# battery_board.net
KiCad netlist of a schematic drawn in EAGLE
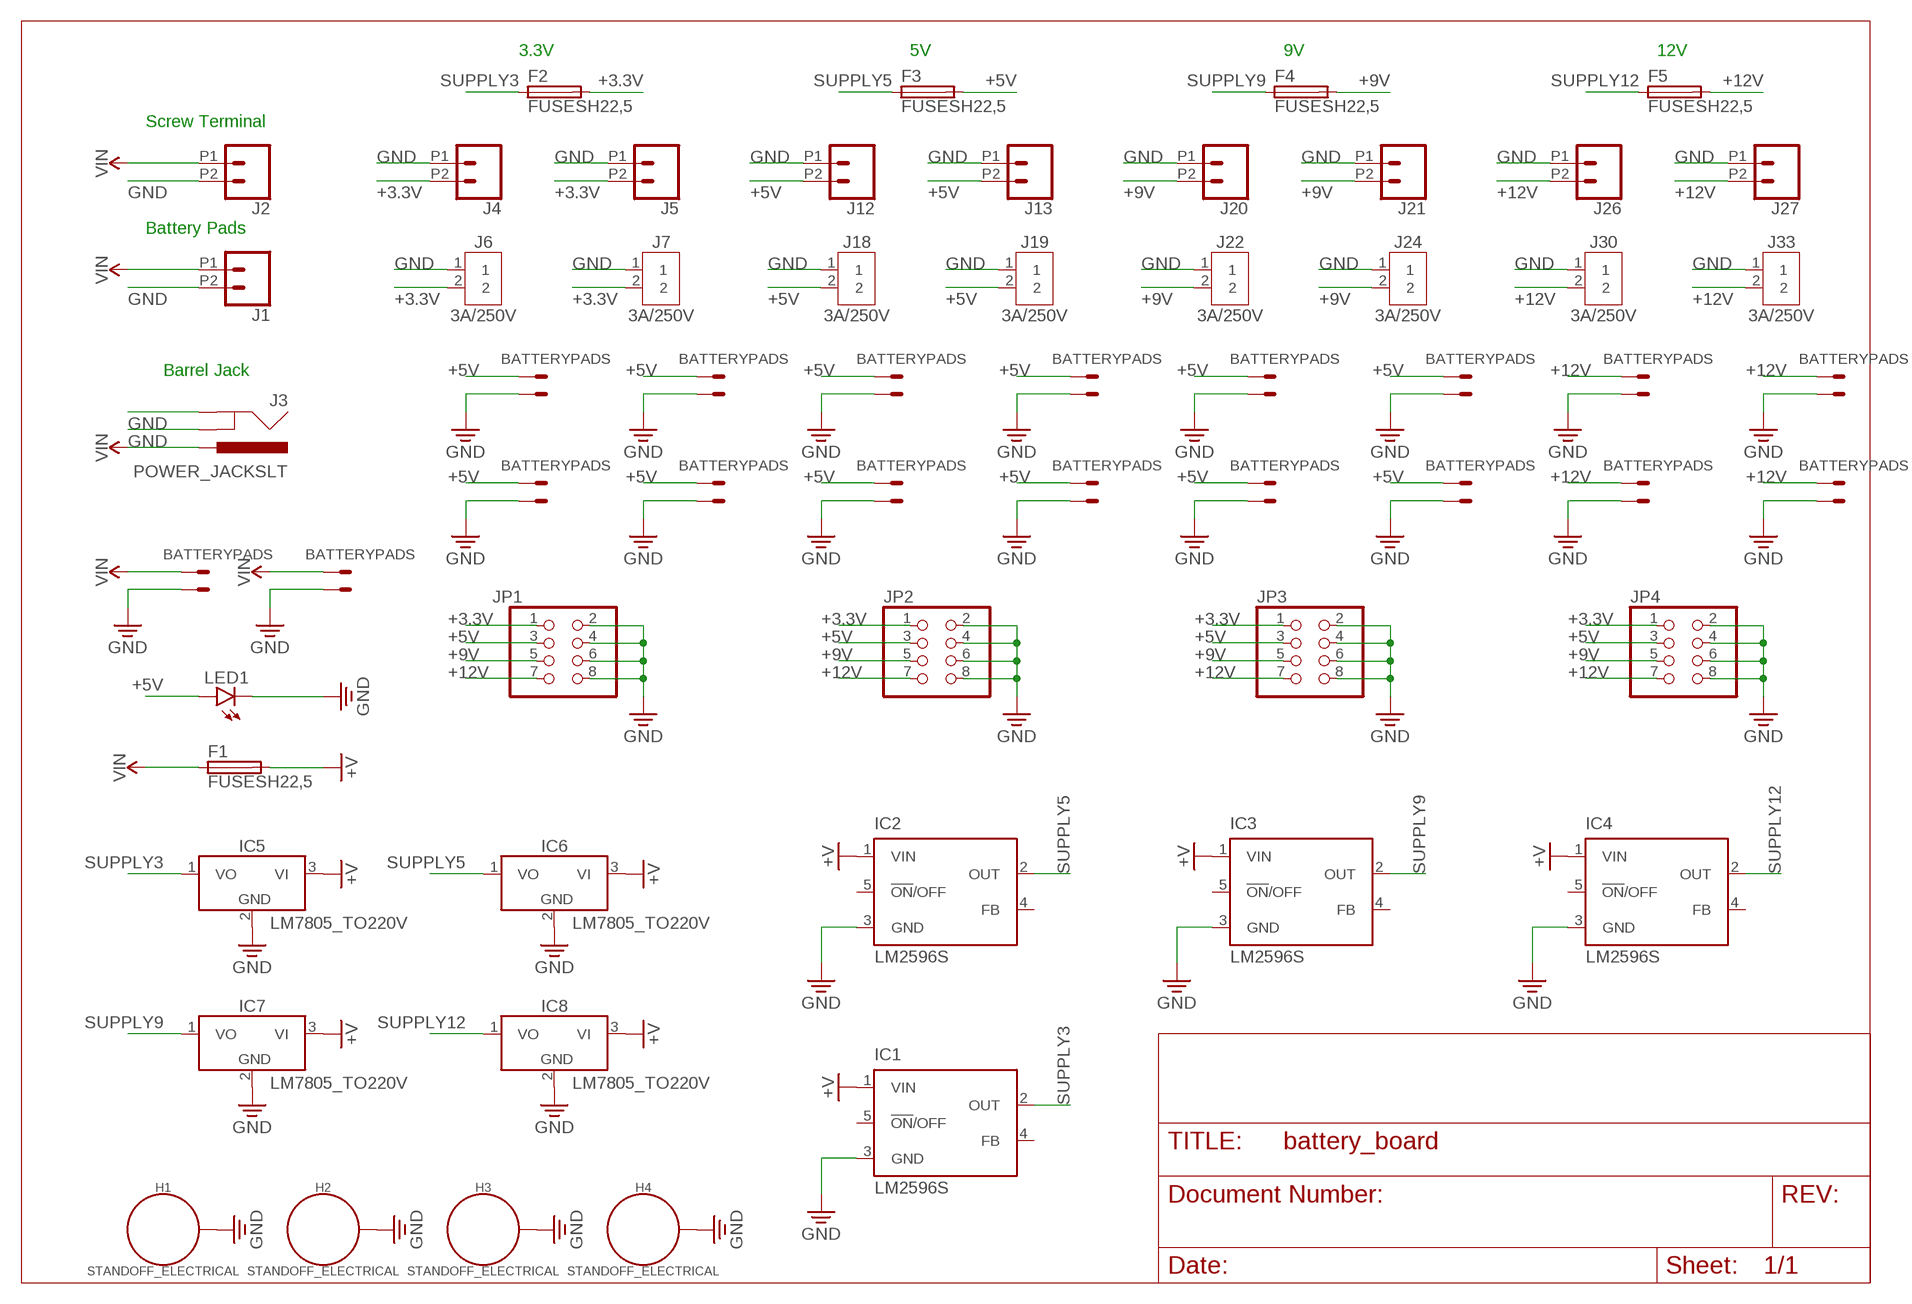
[diagram p0: schematic, sheet 1]

(export (version "E")
  (design (tool "Eeschema 10.0.6"))
  (components
    (comp (ref "BATTERY1")
      (value "BATTERYPADS")
      (footprint "eagle-import:DIODFN1228X508X30-2N")
      (libsource (lib "eagle-import") (part "BATTERYPADS"))
    )
    (comp (ref "BATTERY2")
      (value "BATTERYPADS")
      (footprint "eagle-import:DIODFN1228X508X30-2N")
      (libsource (lib "eagle-import") (part "BATTERYPADS"))
    )
    (comp (ref "F1")
      (value "FUSESH22,5")
      (footprint "eagle-import:SH22,5")
      (libsource (lib "eagle-import") (part "FUSESH22,5"))
    )
    (comp (ref "F2")
      (value "FUSESH22,5")
      (footprint "eagle-import:SH22,5")
      (libsource (lib "eagle-import") (part "FUSESH22,5"))
    )
    (comp (ref "F3")
      (value "FUSESH22,5")
      (footprint "eagle-import:SH22,5")
      (libsource (lib "eagle-import") (part "FUSESH22,5"))
    )
    (comp (ref "F4")
      (value "FUSESH22,5")
      (footprint "eagle-import:SH22,5")
      (libsource (lib "eagle-import") (part "FUSESH22,5"))
    )
    (comp (ref "F5")
      (value "FUSESH22,5")
      (footprint "eagle-import:SH22,5")
      (libsource (lib "eagle-import") (part "FUSESH22,5"))
    )
    (comp (ref "H1")
      (value "STANDOFF_ELECTRICAL")
      (footprint "eagle-import:STANDOFF-ELECTRICAL")
      (libsource (lib "eagle-import") (part "STANDOFF_ELECTRICAL"))
    )
    (comp (ref "H2")
      (value "STANDOFF_ELECTRICAL")
      (footprint "eagle-import:STANDOFF-ELECTRICAL")
      (libsource (lib "eagle-import") (part "STANDOFF_ELECTRICAL"))
    )
    (comp (ref "H3")
      (value "STANDOFF_ELECTRICAL")
      (footprint "eagle-import:STANDOFF-ELECTRICAL")
      (libsource (lib "eagle-import") (part "STANDOFF_ELECTRICAL"))
    )
    (comp (ref "H4")
      (value "STANDOFF_ELECTRICAL")
      (footprint "eagle-import:STANDOFF-ELECTRICAL")
      (libsource (lib "eagle-import") (part "STANDOFF_ELECTRICAL"))
    )
    (comp (ref "IC1")
      (value "LM2596S")
      (footprint "eagle-import:TO263-5")
      (fields (field (name "MF") "NATIONAL SEMICONDUCTOR") (field (name "MPN") "LM2596S-ADJ/NOPB"))
      (libsource (lib "eagle-import") (part "LM2596S"))
    )
    (comp (ref "IC2")
      (value "LM2596S")
      (footprint "eagle-import:TO263-5")
      (fields (field (name "MF") "NATIONAL SEMICONDUCTOR") (field (name "MPN") "LM2596S-ADJ/NOPB"))
      (libsource (lib "eagle-import") (part "LM2596S"))
    )
    (comp (ref "IC3")
      (value "LM2596S")
      (footprint "eagle-import:TO263-5")
      (fields (field (name "MF") "NATIONAL SEMICONDUCTOR") (field (name "MPN") "LM2596S-ADJ/NOPB"))
      (libsource (lib "eagle-import") (part "LM2596S"))
    )
    (comp (ref "IC4")
      (value "LM2596S")
      (footprint "eagle-import:TO263-5")
      (fields (field (name "MF") "NATIONAL SEMICONDUCTOR") (field (name "MPN") "LM2596S-ADJ/NOPB"))
      (libsource (lib "eagle-import") (part "LM2596S"))
    )
    (comp (ref "IC5")
      (value "LM7805_TO220V")
      (footprint "eagle-import:TO220V")
      (fields (field (name "MANUFACTURER") "Generic"))
      (libsource (lib "eagle-import") (part "LM7805_TO220V"))
    )
    (comp (ref "IC6")
      (value "LM7805_TO220V")
      (footprint "eagle-import:TO220V")
      (fields (field (name "MANUFACTURER") "Generic"))
      (libsource (lib "eagle-import") (part "LM7805_TO220V"))
    )
    (comp (ref "IC7")
      (value "LM7805_TO220V")
      (footprint "eagle-import:TO220V")
      (fields (field (name "MANUFACTURER") "Generic"))
      (libsource (lib "eagle-import") (part "LM7805_TO220V"))
    )
    (comp (ref "IC8")
      (value "LM7805_TO220V")
      (footprint "eagle-import:TO220V")
      (fields (field (name "MANUFACTURER") "Generic"))
      (libsource (lib "eagle-import") (part "LM7805_TO220V"))
    )
    (comp (ref "J1")
      (value "CONN_022.54MM_SCREWTERM")
      (footprint "eagle-import:1X02_2.54_SCREWTERM")
      (libsource (lib "eagle-import") (part "CONN_022.54MM_SCREWTERM"))
    )
    (comp (ref "J2")
      (value "CONN_022.54MM_SCREWTERM")
      (footprint "eagle-import:1X02_2.54_SCREWTERM")
      (libsource (lib "eagle-import") (part "CONN_022.54MM_SCREWTERM"))
    )
    (comp (ref "J3")
      (value "POWER_JACKSLT")
      (footprint "eagle-import:POWER_JACK_SLOT")
      (libsource (lib "eagle-import") (part "POWER_JACKSLT"))
    )
    (comp (ref "J4")
      (value "CONN_022.54MM_SCREWTERM")
      (footprint "eagle-import:1X02_2.54_SCREWTERM")
      (libsource (lib "eagle-import") (part "CONN_022.54MM_SCREWTERM"))
    )
    (comp (ref "J5")
      (value "CONN_022.54MM_SCREWTERM")
      (footprint "eagle-import:1X02_2.54_SCREWTERM")
      (libsource (lib "eagle-import") (part "CONN_022.54MM_SCREWTERM"))
    )
    (comp (ref "J6")
      (value "3A/250V")
      (footprint "eagle-import:B2B-XH-A")
      (fields (field (name "MANUFACTURER") "JST (XH CONNECTOR)") (field (name "MPN") "B2B-XH-A"))
      (libsource (lib "eagle-import") (part "B2B-XH-A"))
    )
    (comp (ref "J7")
      (value "3A/250V")
      (footprint "eagle-import:B2B-XH-A")
      (fields (field (name "MANUFACTURER") "JST (XH CONNECTOR)") (field (name "MPN") "B2B-XH-A"))
      (libsource (lib "eagle-import") (part "B2B-XH-A"))
    )
    (comp (ref "J12")
      (value "CONN_022.54MM_SCREWTERM")
      (footprint "eagle-import:1X02_2.54_SCREWTERM")
      (libsource (lib "eagle-import") (part "CONN_022.54MM_SCREWTERM"))
    )
    (comp (ref "J13")
      (value "CONN_022.54MM_SCREWTERM")
      (footprint "eagle-import:1X02_2.54_SCREWTERM")
      (libsource (lib "eagle-import") (part "CONN_022.54MM_SCREWTERM"))
    )
    (comp (ref "J18")
      (value "3A/250V")
      (footprint "eagle-import:B2B-XH-A")
      (fields (field (name "MANUFACTURER") "JST (XH CONNECTOR)") (field (name "MPN") "B2B-XH-A"))
      (libsource (lib "eagle-import") (part "B2B-XH-A"))
    )
    (comp (ref "J19")
      (value "3A/250V")
      (footprint "eagle-import:B2B-XH-A")
      (fields (field (name "MANUFACTURER") "JST (XH CONNECTOR)") (field (name "MPN") "B2B-XH-A"))
      (libsource (lib "eagle-import") (part "B2B-XH-A"))
    )
    (comp (ref "J20")
      (value "CONN_022.54MM_SCREWTERM")
      (footprint "eagle-import:1X02_2.54_SCREWTERM")
      (libsource (lib "eagle-import") (part "CONN_022.54MM_SCREWTERM"))
    )
    (comp (ref "J21")
      (value "CONN_022.54MM_SCREWTERM")
      (footprint "eagle-import:1X02_2.54_SCREWTERM")
      (libsource (lib "eagle-import") (part "CONN_022.54MM_SCREWTERM"))
    )
    (comp (ref "J22")
      (value "3A/250V")
      (footprint "eagle-import:B2B-XH-A")
      (fields (field (name "MANUFACTURER") "JST (XH CONNECTOR)") (field (name "MPN") "B2B-XH-A"))
      (libsource (lib "eagle-import") (part "B2B-XH-A"))
    )
    (comp (ref "J24")
      (value "3A/250V")
      (footprint "eagle-import:B2B-XH-A")
      (fields (field (name "MANUFACTURER") "JST (XH CONNECTOR)") (field (name "MPN") "B2B-XH-A"))
      (libsource (lib "eagle-import") (part "B2B-XH-A"))
    )
    (comp (ref "J26")
      (value "CONN_022.54MM_SCREWTERM")
      (footprint "eagle-import:1X02_2.54_SCREWTERM")
      (libsource (lib "eagle-import") (part "CONN_022.54MM_SCREWTERM"))
    )
    (comp (ref "J27")
      (value "CONN_022.54MM_SCREWTERM")
      (footprint "eagle-import:1X02_2.54_SCREWTERM")
      (libsource (lib "eagle-import") (part "CONN_022.54MM_SCREWTERM"))
    )
    (comp (ref "J30")
      (value "3A/250V")
      (footprint "eagle-import:B2B-XH-A")
      (fields (field (name "MANUFACTURER") "JST (XH CONNECTOR)") (field (name "MPN") "B2B-XH-A"))
      (libsource (lib "eagle-import") (part "B2B-XH-A"))
    )
    (comp (ref "J33")
      (value "3A/250V")
      (footprint "eagle-import:B2B-XH-A")
      (fields (field (name "MANUFACTURER") "JST (XH CONNECTOR)") (field (name "MPN") "B2B-XH-A"))
      (libsource (lib "eagle-import") (part "B2B-XH-A"))
    )
    (comp (ref "JP1")
      (value "PINHD-2X4")
      (footprint "eagle-import:2X04")
      (libsource (lib "eagle-import") (part "PINHD-2X4"))
    )
    (comp (ref "JP2")
      (value "PINHD-2X4")
      (footprint "eagle-import:2X04")
      (libsource (lib "eagle-import") (part "PINHD-2X4"))
    )
    (comp (ref "JP3")
      (value "PINHD-2X4")
      (footprint "eagle-import:2X04")
      (libsource (lib "eagle-import") (part "PINHD-2X4"))
    )
    (comp (ref "JP4")
      (value "PINHD-2X4")
      (footprint "eagle-import:2X04")
      (libsource (lib "eagle-import") (part "PINHD-2X4"))
    )
    (comp (ref "LED1")
      (value "LEDCHIP-LED0805")
      (footprint "eagle-import:CHIP-LED0805")
      (libsource (lib "eagle-import") (part "LEDCHIP-LED0805"))
    )
    (comp (ref "U$1")
      (value "BATTERYPADS")
      (footprint "eagle-import:DIODFN1228X508X30-2N")
      (libsource (lib "eagle-import") (part "BATTERYPADS"))
    )
    (comp (ref "U$2")
      (value "BATTERYPADS")
      (footprint "eagle-import:DIODFN1228X508X30-2N")
      (libsource (lib "eagle-import") (part "BATTERYPADS"))
    )
    (comp (ref "U$3")
      (value "BATTERYPADS")
      (footprint "eagle-import:DIODFN1228X508X30-2N")
      (libsource (lib "eagle-import") (part "BATTERYPADS"))
    )
    (comp (ref "U$4")
      (value "BATTERYPADS")
      (footprint "eagle-import:DIODFN1228X508X30-2N")
      (libsource (lib "eagle-import") (part "BATTERYPADS"))
    )
    (comp (ref "U$5")
      (value "BATTERYPADS")
      (footprint "eagle-import:DIODFN1228X508X30-2N")
      (libsource (lib "eagle-import") (part "BATTERYPADS"))
    )
    (comp (ref "U$6")
      (value "BATTERYPADS")
      (footprint "eagle-import:DIODFN1228X508X30-2N")
      (libsource (lib "eagle-import") (part "BATTERYPADS"))
    )
    (comp (ref "U$7")
      (value "BATTERYPADS")
      (footprint "eagle-import:DIODFN1228X508X30-2N")
      (libsource (lib "eagle-import") (part "BATTERYPADS"))
    )
    (comp (ref "U$8")
      (value "BATTERYPADS")
      (footprint "eagle-import:DIODFN1228X508X30-2N")
      (libsource (lib "eagle-import") (part "BATTERYPADS"))
    )
    (comp (ref "U$9")
      (value "BATTERYPADS")
      (footprint "eagle-import:DIODFN1228X508X30-2N")
      (libsource (lib "eagle-import") (part "BATTERYPADS"))
    )
    (comp (ref "U$10")
      (value "BATTERYPADS")
      (footprint "eagle-import:DIODFN1228X508X30-2N")
      (libsource (lib "eagle-import") (part "BATTERYPADS"))
    )
    (comp (ref "U$11")
      (value "BATTERYPADS")
      (footprint "eagle-import:DIODFN1228X508X30-2N")
      (libsource (lib "eagle-import") (part "BATTERYPADS"))
    )
    (comp (ref "U$12")
      (value "BATTERYPADS")
      (footprint "eagle-import:DIODFN1228X508X30-2N")
      (libsource (lib "eagle-import") (part "BATTERYPADS"))
    )
    (comp (ref "U$13")
      (value "BATTERYPADS")
      (footprint "eagle-import:DIODFN1228X508X30-2N")
      (libsource (lib "eagle-import") (part "BATTERYPADS"))
    )
    (comp (ref "U$14")
      (value "BATTERYPADS")
      (footprint "eagle-import:DIODFN1228X508X30-2N")
      (libsource (lib "eagle-import") (part "BATTERYPADS"))
    )
    (comp (ref "U$15")
      (value "BATTERYPADS")
      (footprint "eagle-import:DIODFN1228X508X30-2N")
      (libsource (lib "eagle-import") (part "BATTERYPADS"))
    )
    (comp (ref "U$16")
      (value "BATTERYPADS")
      (footprint "eagle-import:DIODFN1228X508X30-2N")
      (libsource (lib "eagle-import") (part "BATTERYPADS"))
    )
  )
  (nets
    (net (code "1") (name "+V") (class "Default")
      (node (ref "F1") (pin "2") (pinfunction "2_2") (pintype "passive"))
      (node (ref "IC1") (pin "1") (pinfunction "VIN_1") (pintype "input"))
      (node (ref "IC2") (pin "1") (pinfunction "VIN_1") (pintype "input"))
      (node (ref "IC3") (pin "1") (pinfunction "VIN_1") (pintype "input"))
      (node (ref "IC4") (pin "1") (pinfunction "VIN_1") (pintype "input"))
      (node (ref "IC5") (pin "3") (pinfunction "VI_3") (pintype "output"))
      (node (ref "IC6") (pin "3") (pinfunction "VI_3") (pintype "output"))
      (node (ref "IC7") (pin "3") (pinfunction "VI_3") (pintype "output"))
      (node (ref "IC8") (pin "3") (pinfunction "VI_3") (pintype "output"))
    )
    (net (code "2") (name "/+3.3V") (class "Default")
      (node (ref "F2") (pin "2") (pinfunction "2_2") (pintype "passive"))
      (node (ref "J4") (pin "P2") (pinfunction "2_P2") (pintype "passive"))
      (node (ref "J5") (pin "P2") (pinfunction "2_P2") (pintype "passive"))
      (node (ref "J6") (pin "2") (pinfunction "2_2") (pintype "bidirectional"))
      (node (ref "J7") (pin "2") (pinfunction "2_2") (pintype "bidirectional"))
      (node (ref "JP1") (pin "1") (pinfunction "1_1") (pintype "passive"))
      (node (ref "JP2") (pin "1") (pinfunction "1_1") (pintype "passive"))
      (node (ref "JP3") (pin "1") (pinfunction "1_1") (pintype "passive"))
      (node (ref "JP4") (pin "1") (pinfunction "1_1") (pintype "passive"))
    )
    (net (code "3") (name "/+5V") (class "Default")
      (node (ref "F3") (pin "2") (pinfunction "2_2") (pintype "passive"))
      (node (ref "J12") (pin "P2") (pinfunction "2_P2") (pintype "passive"))
      (node (ref "J13") (pin "P2") (pinfunction "2_P2") (pintype "passive"))
      (node (ref "J18") (pin "2") (pinfunction "2_2") (pintype "bidirectional"))
      (node (ref "J19") (pin "2") (pinfunction "2_2") (pintype "bidirectional"))
      (node (ref "JP1") (pin "3") (pinfunction "3_3") (pintype "passive"))
      (node (ref "JP2") (pin "3") (pinfunction "3_3") (pintype "passive"))
      (node (ref "JP3") (pin "3") (pinfunction "3_3") (pintype "passive"))
      (node (ref "JP4") (pin "3") (pinfunction "3_3") (pintype "passive"))
      (node (ref "LED1") (pin "A") (pinfunction "A_A") (pintype "passive"))
      (node (ref "U$1") (pin "VIN") (pinfunction "VIN_VIN") (pintype "passive"))
      (node (ref "U$13") (pin "VIN") (pinfunction "VIN_VIN") (pintype "passive"))
      (node (ref "U$14") (pin "VIN") (pinfunction "VIN_VIN") (pintype "passive"))
      (node (ref "U$15") (pin "VIN") (pinfunction "VIN_VIN") (pintype "passive"))
      (node (ref "U$16") (pin "VIN") (pinfunction "VIN_VIN") (pintype "passive"))
      (node (ref "U$2") (pin "VIN") (pinfunction "VIN_VIN") (pintype "passive"))
      (node (ref "U$3") (pin "VIN") (pinfunction "VIN_VIN") (pintype "passive"))
      (node (ref "U$4") (pin "VIN") (pinfunction "VIN_VIN") (pintype "passive"))
      (node (ref "U$5") (pin "VIN") (pinfunction "VIN_VIN") (pintype "passive"))
      (node (ref "U$6") (pin "VIN") (pinfunction "VIN_VIN") (pintype "passive"))
      (node (ref "U$7") (pin "VIN") (pinfunction "VIN_VIN") (pintype "passive"))
      (node (ref "U$8") (pin "VIN") (pinfunction "VIN_VIN") (pintype "passive"))
    )
    (net (code "4") (name "/+9V") (class "Default")
      (node (ref "F4") (pin "2") (pinfunction "2_2") (pintype "passive"))
      (node (ref "J20") (pin "P2") (pinfunction "2_P2") (pintype "passive"))
      (node (ref "J21") (pin "P2") (pinfunction "2_P2") (pintype "passive"))
      (node (ref "J22") (pin "2") (pinfunction "2_2") (pintype "bidirectional"))
      (node (ref "J24") (pin "2") (pinfunction "2_2") (pintype "bidirectional"))
      (node (ref "JP1") (pin "5") (pinfunction "5_5") (pintype "passive"))
      (node (ref "JP2") (pin "5") (pinfunction "5_5") (pintype "passive"))
      (node (ref "JP3") (pin "5") (pinfunction "5_5") (pintype "passive"))
      (node (ref "JP4") (pin "5") (pinfunction "5_5") (pintype "passive"))
    )
    (net (code "5") (name "/+12V") (class "Default")
      (node (ref "F5") (pin "2") (pinfunction "2_2") (pintype "passive"))
      (node (ref "J26") (pin "P2") (pinfunction "2_P2") (pintype "passive"))
      (node (ref "J27") (pin "P2") (pinfunction "2_P2") (pintype "passive"))
      (node (ref "J30") (pin "2") (pinfunction "2_2") (pintype "bidirectional"))
      (node (ref "J33") (pin "2") (pinfunction "2_2") (pintype "bidirectional"))
      (node (ref "JP1") (pin "7") (pinfunction "7_7") (pintype "passive"))
      (node (ref "JP2") (pin "7") (pinfunction "7_7") (pintype "passive"))
      (node (ref "JP3") (pin "7") (pinfunction "7_7") (pintype "passive"))
      (node (ref "JP4") (pin "7") (pinfunction "7_7") (pintype "passive"))
      (node (ref "U$10") (pin "VIN") (pinfunction "VIN_VIN") (pintype "passive"))
      (node (ref "U$11") (pin "VIN") (pinfunction "VIN_VIN") (pintype "passive"))
      (node (ref "U$12") (pin "VIN") (pinfunction "VIN_VIN") (pintype "passive"))
      (node (ref "U$9") (pin "VIN") (pinfunction "VIN_VIN") (pintype "passive"))
    )
    (net (code "6") (name "/SUPPLY3") (class "Default")
      (node (ref "F2") (pin "1") (pinfunction "1_1") (pintype "passive"))
      (node (ref "IC1") (pin "2") (pinfunction "OUT_2") (pintype "output"))
      (node (ref "IC5") (pin "1") (pinfunction "VO_1") (pintype "input"))
    )
    (net (code "7") (name "/SUPPLY5") (class "Default")
      (node (ref "F3") (pin "1") (pinfunction "1_1") (pintype "passive"))
      (node (ref "IC2") (pin "2") (pinfunction "OUT_2") (pintype "output"))
      (node (ref "IC6") (pin "1") (pinfunction "VO_1") (pintype "input"))
    )
    (net (code "8") (name "/SUPPLY9") (class "Default")
      (node (ref "F4") (pin "1") (pinfunction "1_1") (pintype "passive"))
      (node (ref "IC3") (pin "2") (pinfunction "OUT_2") (pintype "output"))
      (node (ref "IC7") (pin "1") (pinfunction "VO_1") (pintype "input"))
    )
    (net (code "9") (name "/SUPPLY12") (class "Default")
      (node (ref "F5") (pin "1") (pinfunction "1_1") (pintype "passive"))
      (node (ref "IC4") (pin "2") (pinfunction "OUT_2") (pintype "output"))
      (node (ref "IC8") (pin "1") (pinfunction "VO_1") (pintype "input"))
    )
    (net (code "10") (name "GND") (class "Default")
      (node (ref "BATTERY1") (pin "GND") (pinfunction "GND_GND") (pintype "passive"))
      (node (ref "BATTERY2") (pin "GND") (pinfunction "GND_GND") (pintype "passive"))
      (node (ref "H1") (pin "P1") (pinfunction "P$1_P1") (pintype "bidirectional"))
      (node (ref "H2") (pin "P1") (pinfunction "P$1_P1") (pintype "bidirectional"))
      (node (ref "H3") (pin "P1") (pinfunction "P$1_P1") (pintype "bidirectional"))
      (node (ref "H4") (pin "P1") (pinfunction "P$1_P1") (pintype "bidirectional"))
      (node (ref "IC1") (pin "3") (pinfunction "GND_3") (pintype "power_in"))
      (node (ref "IC2") (pin "3") (pinfunction "GND_3") (pintype "power_in"))
      (node (ref "IC3") (pin "3") (pinfunction "GND_3") (pintype "power_in"))
      (node (ref "IC4") (pin "3") (pinfunction "GND_3") (pintype "power_in"))
      (node (ref "IC5") (pin "2") (pinfunction "GND_2") (pintype "passive"))
      (node (ref "IC6") (pin "2") (pinfunction "GND_2") (pintype "passive"))
      (node (ref "IC7") (pin "2") (pinfunction "GND_2") (pintype "passive"))
      (node (ref "IC8") (pin "2") (pinfunction "GND_2") (pintype "passive"))
      (node (ref "J1") (pin "P2") (pinfunction "2_P2") (pintype "passive"))
      (node (ref "J12") (pin "P1") (pinfunction "1_P1") (pintype "passive"))
      (node (ref "J13") (pin "P1") (pinfunction "1_P1") (pintype "passive"))
      (node (ref "J18") (pin "1") (pinfunction "1_1") (pintype "bidirectional"))
      (node (ref "J19") (pin "1") (pinfunction "1_1") (pintype "bidirectional"))
      (node (ref "J2") (pin "P2") (pinfunction "2_P2") (pintype "passive"))
      (node (ref "J20") (pin "P1") (pinfunction "1_P1") (pintype "passive"))
      (node (ref "J21") (pin "P1") (pinfunction "1_P1") (pintype "passive"))
      (node (ref "J22") (pin "1") (pinfunction "1_1") (pintype "bidirectional"))
      (node (ref "J24") (pin "1") (pinfunction "1_1") (pintype "bidirectional"))
      (node (ref "J26") (pin "P1") (pinfunction "1_P1") (pintype "passive"))
      (node (ref "J27") (pin "P1") (pinfunction "1_P1") (pintype "passive"))
      (node (ref "J3") (pin "GND@1") (pinfunction "GNDBREAK_GND@1") (pintype "bidirectional"))
      (node (ref "J3") (pin "GND@2") (pinfunction "GND_GND@2") (pintype "bidirectional"))
      (node (ref "J30") (pin "1") (pinfunction "1_1") (pintype "bidirectional"))
      (node (ref "J33") (pin "1") (pinfunction "1_1") (pintype "bidirectional"))
      (node (ref "J4") (pin "P1") (pinfunction "1_P1") (pintype "passive"))
      (node (ref "J5") (pin "P1") (pinfunction "1_P1") (pintype "passive"))
      (node (ref "J6") (pin "1") (pinfunction "1_1") (pintype "bidirectional"))
      (node (ref "J7") (pin "1") (pinfunction "1_1") (pintype "bidirectional"))
      (node (ref "JP1") (pin "2") (pinfunction "2_2") (pintype "passive"))
      (node (ref "JP1") (pin "4") (pinfunction "4_4") (pintype "passive"))
      (node (ref "JP1") (pin "6") (pinfunction "6_6") (pintype "passive"))
      (node (ref "JP1") (pin "8") (pinfunction "8_8") (pintype "passive"))
      (node (ref "JP2") (pin "2") (pinfunction "2_2") (pintype "passive"))
      (node (ref "JP2") (pin "4") (pinfunction "4_4") (pintype "passive"))
      (node (ref "JP2") (pin "6") (pinfunction "6_6") (pintype "passive"))
      (node (ref "JP2") (pin "8") (pinfunction "8_8") (pintype "passive"))
      (node (ref "JP3") (pin "2") (pinfunction "2_2") (pintype "passive"))
      (node (ref "JP3") (pin "4") (pinfunction "4_4") (pintype "passive"))
      (node (ref "JP3") (pin "6") (pinfunction "6_6") (pintype "passive"))
      (node (ref "JP3") (pin "8") (pinfunction "8_8") (pintype "passive"))
      (node (ref "JP4") (pin "2") (pinfunction "2_2") (pintype "passive"))
      (node (ref "JP4") (pin "4") (pinfunction "4_4") (pintype "passive"))
      (node (ref "JP4") (pin "6") (pinfunction "6_6") (pintype "passive"))
      (node (ref "JP4") (pin "8") (pinfunction "8_8") (pintype "passive"))
      (node (ref "LED1") (pin "C") (pinfunction "C_C") (pintype "passive"))
      (node (ref "U$1") (pin "GND") (pinfunction "GND_GND") (pintype "passive"))
      (node (ref "U$10") (pin "GND") (pinfunction "GND_GND") (pintype "passive"))
      (node (ref "U$11") (pin "GND") (pinfunction "GND_GND") (pintype "passive"))
      (node (ref "U$12") (pin "GND") (pinfunction "GND_GND") (pintype "passive"))
      (node (ref "U$13") (pin "GND") (pinfunction "GND_GND") (pintype "passive"))
      (node (ref "U$14") (pin "GND") (pinfunction "GND_GND") (pintype "passive"))
      (node (ref "U$15") (pin "GND") (pinfunction "GND_GND") (pintype "passive"))
      (node (ref "U$16") (pin "GND") (pinfunction "GND_GND") (pintype "passive"))
      (node (ref "U$2") (pin "GND") (pinfunction "GND_GND") (pintype "passive"))
      (node (ref "U$3") (pin "GND") (pinfunction "GND_GND") (pintype "passive"))
      (node (ref "U$4") (pin "GND") (pinfunction "GND_GND") (pintype "passive"))
      (node (ref "U$5") (pin "GND") (pinfunction "GND_GND") (pintype "passive"))
      (node (ref "U$6") (pin "GND") (pinfunction "GND_GND") (pintype "passive"))
      (node (ref "U$7") (pin "GND") (pinfunction "GND_GND") (pintype "passive"))
      (node (ref "U$8") (pin "GND") (pinfunction "GND_GND") (pintype "passive"))
      (node (ref "U$9") (pin "GND") (pinfunction "GND_GND") (pintype "passive"))
    )
    (net (code "11") (name "VIN") (class "Default")
      (node (ref "BATTERY1") (pin "VIN") (pinfunction "VIN_VIN") (pintype "passive"))
      (node (ref "BATTERY2") (pin "VIN") (pinfunction "VIN_VIN") (pintype "passive"))
      (node (ref "F1") (pin "1") (pinfunction "1_1") (pintype "passive"))
      (node (ref "J1") (pin "P1") (pinfunction "1_P1") (pintype "passive"))
      (node (ref "J2") (pin "P1") (pinfunction "1_P1") (pintype "passive"))
      (node (ref "J3") (pin "PWR") (pinfunction "PWR_PWR") (pintype "bidirectional"))
    )
    (net (code "12") (name "unconnected-(IC1-FB-Pad4)") (class "Default")
      (node (ref "IC1") (pin "4") (pinfunction "FB_4") (pintype "input"))
    )
    (net (code "13") (name "unconnected-(IC1-~{ON}{slash}OFF-Pad5)") (class "Default")
      (node (ref "IC1") (pin "5") (pinfunction "~{ON}/OFF_5") (pintype "input"))
    )
    (net (code "14") (name "unconnected-(IC2-FB-Pad4)") (class "Default")
      (node (ref "IC2") (pin "4") (pinfunction "FB_4") (pintype "input"))
    )
    (net (code "15") (name "unconnected-(IC2-~{ON}{slash}OFF-Pad5)") (class "Default")
      (node (ref "IC2") (pin "5") (pinfunction "~{ON}/OFF_5") (pintype "input"))
    )
    (net (code "16") (name "unconnected-(IC3-FB-Pad4)") (class "Default")
      (node (ref "IC3") (pin "4") (pinfunction "FB_4") (pintype "input"))
    )
    (net (code "17") (name "unconnected-(IC3-~{ON}{slash}OFF-Pad5)") (class "Default")
      (node (ref "IC3") (pin "5") (pinfunction "~{ON}/OFF_5") (pintype "input"))
    )
    (net (code "18") (name "unconnected-(IC4-FB-Pad4)") (class "Default")
      (node (ref "IC4") (pin "4") (pinfunction "FB_4") (pintype "input"))
    )
    (net (code "19") (name "unconnected-(IC4-~{ON}{slash}OFF-Pad5)") (class "Default")
      (node (ref "IC4") (pin "5") (pinfunction "~{ON}/OFF_5") (pintype "input"))
    )
  )
)
